# miscellaneous.net
KiCad netlist of a schematic drawn in Altium Designer
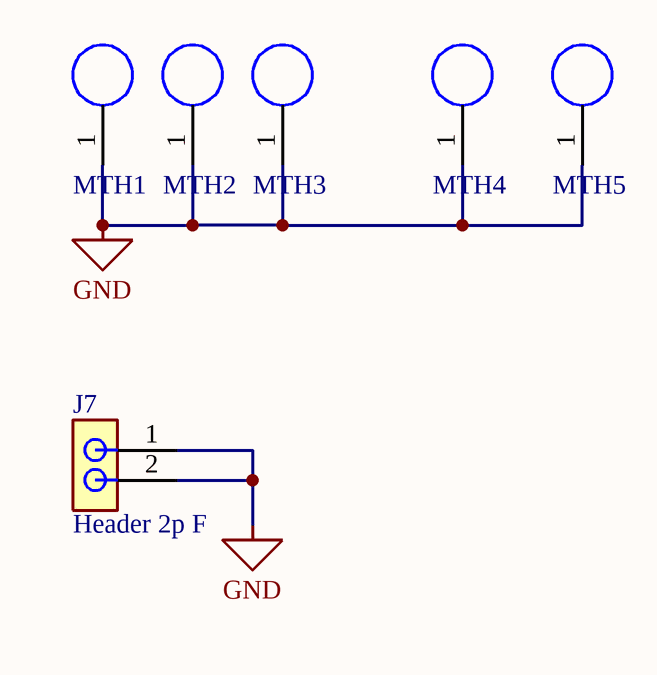
[diagram p0: miscellaneous.SchDoc]

(export (version "E")
  (design (tool "Eeschema 10.0.6"))
  (components
    (comp (ref "J7")
      (value "Header 2p F")
      (footprint "Pin header 2p - F")
      (description "Connector")
      (fields (field (name "MANUFACTURER_PART_NUMBER") "DS1021-1*2SF11-B"))
      (libsource (lib "Kubikova ultra knihovna") (part "Pin header 2p_F"))
    )
    (comp (ref "MTH1")
      (value "Hole")
      (footprint "3.2/6 MM")
      (description "Universal mounting hole plated")
      (libsource (lib "Kubikova ultra knihovna") (part "Hole"))
    )
    (comp (ref "MTH2")
      (value "Hole")
      (footprint "3.2/6 MM")
      (description "Universal mounting hole plated")
      (libsource (lib "Kubikova ultra knihovna") (part "Hole"))
    )
    (comp (ref "MTH3")
      (value "Hole")
      (footprint "3.2/6 MM")
      (description "Universal mounting hole plated")
      (libsource (lib "Kubikova ultra knihovna") (part "Hole"))
    )
    (comp (ref "MTH4")
      (value "Hole")
      (footprint "3.2/6 MM")
      (description "Universal mounting hole plated")
      (libsource (lib "Kubikova ultra knihovna") (part "Hole"))
    )
    (comp (ref "MTH5")
      (value "Hole")
      (footprint "3.2/6 MM")
      (description "Universal mounting hole plated")
      (libsource (lib "Kubikova ultra knihovna") (part "Hole"))
    )
  )
  (nets
    (net (code "1") (name "GND") (class "Default")
      (node (ref "J7") (pin "1") (pinfunction "1_1") (pintype "passive"))
      (node (ref "J7") (pin "2") (pinfunction "2_2") (pintype "passive"))
      (node (ref "MTH1") (pin "1") (pintype "passive"))
      (node (ref "MTH2") (pin "1") (pintype "passive"))
      (node (ref "MTH3") (pin "1") (pintype "passive"))
      (node (ref "MTH4") (pin "1") (pintype "passive"))
      (node (ref "MTH5") (pin "1") (pintype "passive"))
    )
  )
)
